# ZigUP.net
KiCad netlist of a schematic drawn in EAGLE
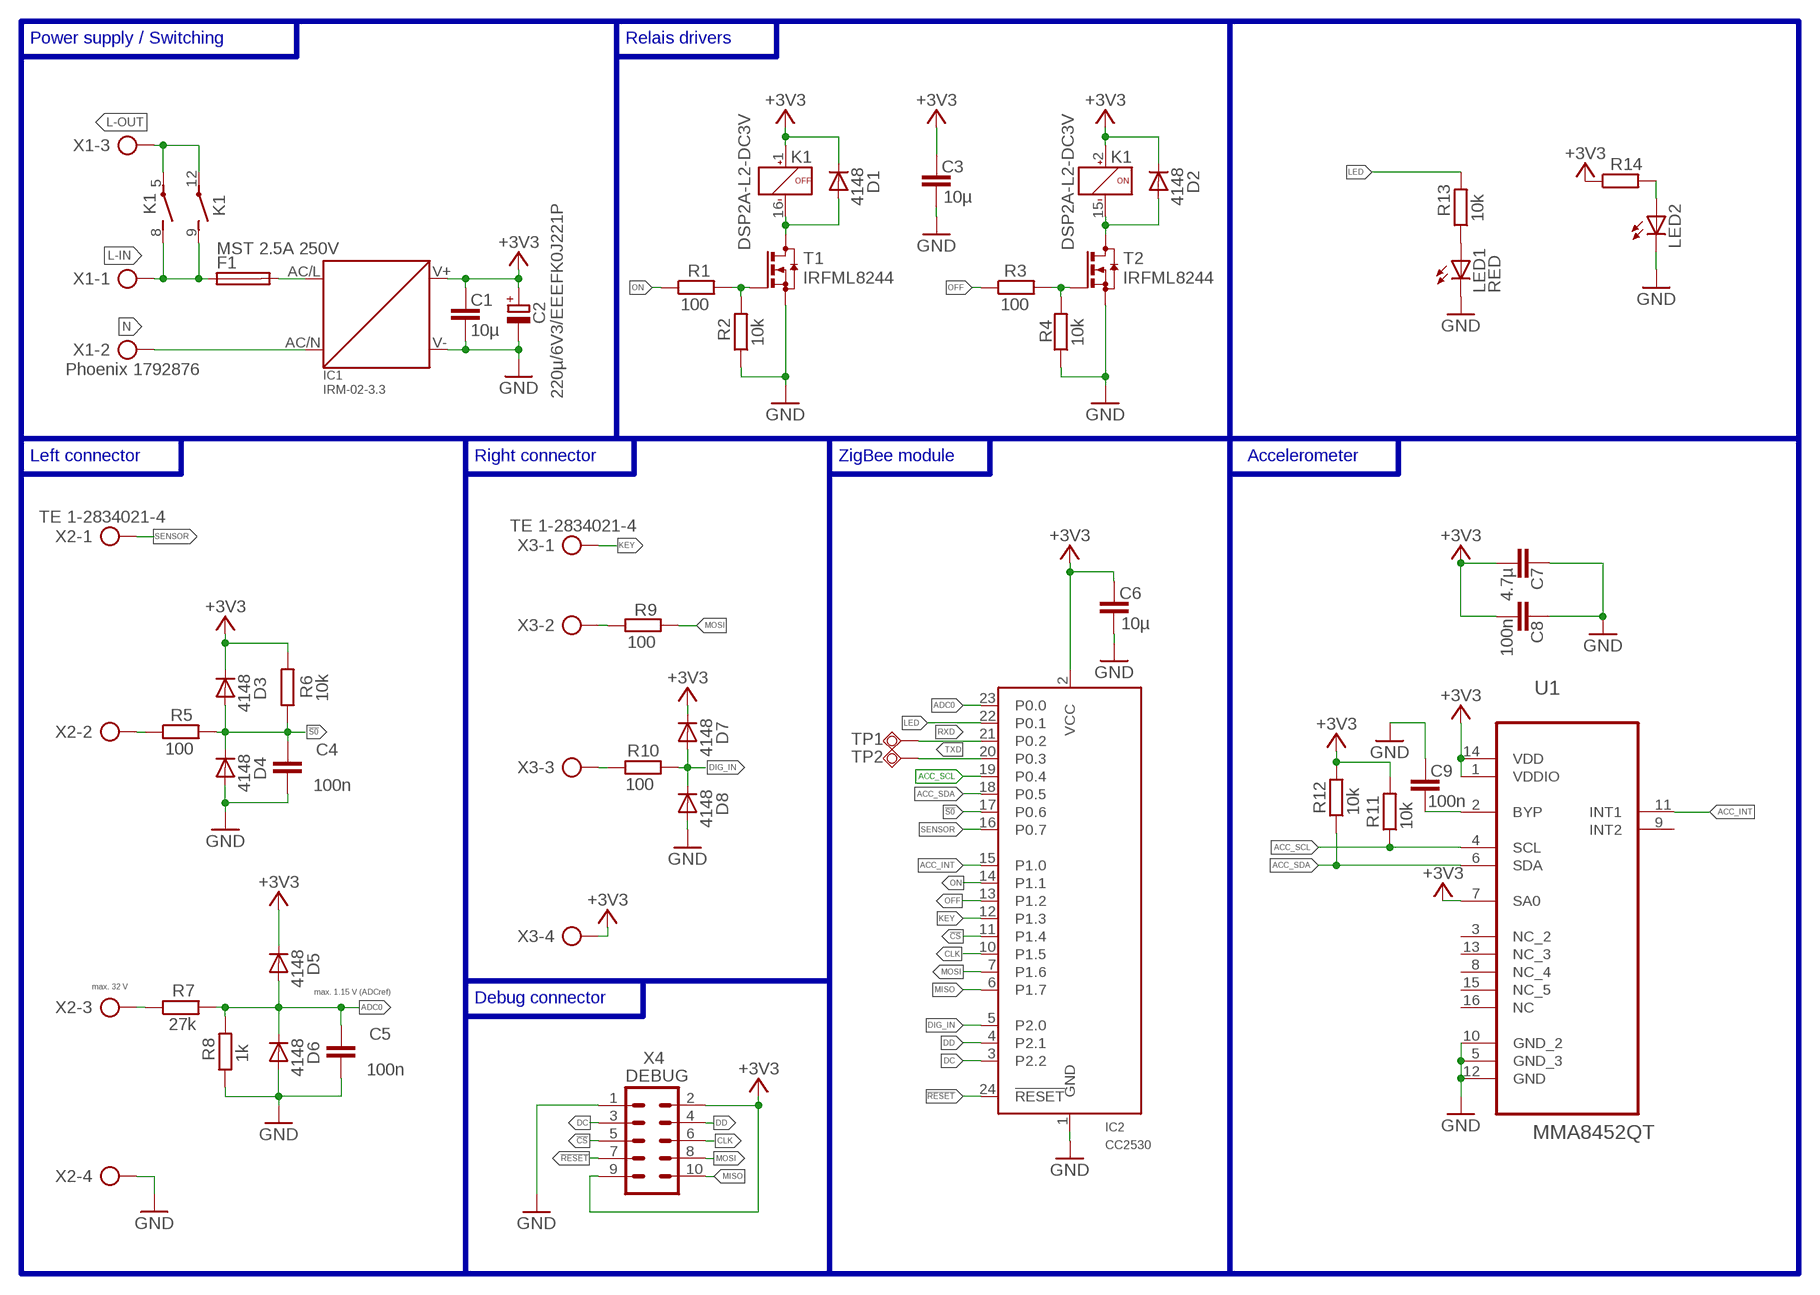
[diagram p0: schematic, sheet 1]

(export (version "E")
  (design (tool "Eeschema 10.0.6"))
  (components
    (comp (ref "C1")
      (value "10µ")
      (footprint "eagle-import:C0805")
      (libsource (lib "eagle-import") (part "C-EUC0805"))
    )
    (comp (ref "C2")
      (value "220µ/6V3/EEEFK0J221P")
      (footprint "eagle-import:E2,5-6")
      (libsource (lib "eagle-import") (part "CPOL-EUE2.5-6"))
    )
    (comp (ref "C3")
      (value "10µ")
      (footprint "eagle-import:C0805")
      (libsource (lib "eagle-import") (part "C-EUC0805"))
    )
    (comp (ref "C4")
      (value "100n")
      (footprint "eagle-import:C0805")
      (libsource (lib "eagle-import") (part "C-EUC0805"))
    )
    (comp (ref "C5")
      (value "100n")
      (footprint "eagle-import:C0805")
      (libsource (lib "eagle-import") (part "C-EUC0805"))
    )
    (comp (ref "C6")
      (value "10µ")
      (footprint "eagle-import:C0805")
      (libsource (lib "eagle-import") (part "C-EUC0805"))
    )
    (comp (ref "C7")
      (value "4.7µ")
      (footprint "eagle-import:C0805")
      (libsource (lib "eagle-import") (part "C-EUC0805"))
    )
    (comp (ref "C8")
      (value "100n")
      (footprint "eagle-import:C0805")
      (libsource (lib "eagle-import") (part "C-EUC0805"))
    )
    (comp (ref "C9")
      (value "100n")
      (footprint "eagle-import:C0805")
      (libsource (lib "eagle-import") (part "C-EUC0805"))
    )
    (comp (ref "D1")
      (value "4148")
      (footprint "eagle-import:1206")
      (libsource (lib "eagle-import") (part "TS4148"))
    )
    (comp (ref "D2")
      (value "4148")
      (footprint "eagle-import:1206")
      (libsource (lib "eagle-import") (part "TS4148"))
    )
    (comp (ref "D3")
      (value "4148")
      (footprint "eagle-import:1206")
      (libsource (lib "eagle-import") (part "TS4148"))
    )
    (comp (ref "D4")
      (value "4148")
      (footprint "eagle-import:1206")
      (libsource (lib "eagle-import") (part "TS4148"))
    )
    (comp (ref "D5")
      (value "4148")
      (footprint "eagle-import:1206")
      (libsource (lib "eagle-import") (part "TS4148"))
    )
    (comp (ref "D6")
      (value "4148")
      (footprint "eagle-import:1206")
      (libsource (lib "eagle-import") (part "TS4148"))
    )
    (comp (ref "D7")
      (value "4148")
      (footprint "eagle-import:1206")
      (libsource (lib "eagle-import") (part "TS4148"))
    )
    (comp (ref "D8")
      (value "4148")
      (footprint "eagle-import:1206")
      (libsource (lib "eagle-import") (part "TS4148"))
    )
    (comp (ref "F1")
      (value "MST 2.5A 250V")
      (footprint "eagle-import:MST")
      (libsource (lib "eagle-import") (part "MST"))
    )
    (comp (ref "IC1")
      (value "IRM-02-3.3")
      (footprint "eagle-import:IRM-01")
      (libsource (lib "eagle-import") (part "IRM-01"))
    )
    (comp (ref "IC2")
      (value "CC2530")
      (footprint "eagle-import:E18-MS1-PCB")
      (libsource (lib "eagle-import") (part "CC2530THT"))
    )
    (comp (ref "K1")
      (value "DSP2A-L2-DC3V")
      (footprint "eagle-import:DSP2A-L2")
      (libsource (lib "eagle-import") (part "DSP2A-L2"))
    )
    (comp (ref "LED1")
      (value "RED")
      (footprint "eagle-import:LED3MM")
      (libsource (lib "eagle-import") (part "LED3MM"))
    )
    (comp (ref "LED2")
      (value "LEDSML0805")
      (footprint "eagle-import:SML0805")
      (libsource (lib "eagle-import") (part "LEDSML0805"))
    )
    (comp (ref "R1")
      (value "100")
      (footprint "eagle-import:R0805")
      (libsource (lib "eagle-import") (part "R-EU_R0805"))
    )
    (comp (ref "R2")
      (value "10k")
      (footprint "eagle-import:R0805")
      (libsource (lib "eagle-import") (part "R-EU_R0805"))
    )
    (comp (ref "R3")
      (value "100")
      (footprint "eagle-import:R0805")
      (libsource (lib "eagle-import") (part "R-EU_R0805"))
    )
    (comp (ref "R4")
      (value "10k")
      (footprint "eagle-import:R0805")
      (libsource (lib "eagle-import") (part "R-EU_R0805"))
    )
    (comp (ref "R5")
      (value "100")
      (footprint "eagle-import:R0805")
      (libsource (lib "eagle-import") (part "R-EU_R0805"))
    )
    (comp (ref "R6")
      (value "10k")
      (footprint "eagle-import:R0805")
      (libsource (lib "eagle-import") (part "R-EU_R0805"))
    )
    (comp (ref "R7")
      (value "27k")
      (footprint "eagle-import:R0805")
      (libsource (lib "eagle-import") (part "R-EU_R0805"))
    )
    (comp (ref "R8")
      (value "1k")
      (footprint "eagle-import:R0805")
      (libsource (lib "eagle-import") (part "R-EU_R0805"))
    )
    (comp (ref "R9")
      (value "100")
      (footprint "eagle-import:R0805")
      (libsource (lib "eagle-import") (part "R-EU_R0805"))
    )
    (comp (ref "R10")
      (value "100")
      (footprint "eagle-import:R0805")
      (libsource (lib "eagle-import") (part "R-EU_R0805"))
    )
    (comp (ref "R11")
      (value "10k")
      (footprint "eagle-import:R0805")
      (libsource (lib "eagle-import") (part "R-EU_R0805"))
    )
    (comp (ref "R12")
      (value "10k")
      (footprint "eagle-import:R0805")
      (libsource (lib "eagle-import") (part "R-EU_R0805"))
    )
    (comp (ref "R13")
      (value "10k")
      (footprint "eagle-import:R0805")
      (libsource (lib "eagle-import") (part "R-EU_R0805"))
    )
    (comp (ref "R14")
      (value "R-EU_R0805")
      (footprint "eagle-import:R0805")
      (libsource (lib "eagle-import") (part "R-EU_R0805"))
    )
    (comp (ref "T1")
      (value "IRFML8244")
      (footprint "eagle-import:SOT23")
      (libsource (lib "eagle-import") (part "BSS123"))
    )
    (comp (ref "T2")
      (value "IRFML8244")
      (footprint "eagle-import:SOT23")
      (libsource (lib "eagle-import") (part "BSS123"))
    )
    (comp (ref "TP1")
      (value "RX")
      (footprint "eagle-import:TP15SQ")
      (libsource (lib "eagle-import") (part "TPSQTP15SQ"))
    )
    (comp (ref "TP2")
      (value "TX")
      (footprint "eagle-import:TP15SQ")
      (libsource (lib "eagle-import") (part "TPSQTP15SQ"))
    )
    (comp (ref "U1")
      (value "MMA8452QT")
      (footprint "eagle-import:QFN50P300X300X100-16N")
      (fields (field (name "MPN") "MMA8452QT "))
      (libsource (lib "eagle-import") (part "MMA8452QT"))
    )
    (comp (ref "X1")
      (value "Phoenix 1792876")
      (footprint "eagle-import:PTS-3")
      (libsource (lib "eagle-import") (part "PTS3"))
    )
    (comp (ref "X2")
      (value "TE 1-2834021-4")
      (footprint "eagle-import:MSC4")
      (libsource (lib "eagle-import") (part "MSC4"))
    )
    (comp (ref "X3")
      (value "TE 1-2834021-4")
      (footprint "eagle-import:MSC4")
      (libsource (lib "eagle-import") (part "MSC4"))
    )
    (comp (ref "X4")
      (value "DEBUG")
      (footprint "eagle-import:MA05-2")
      (libsource (lib "eagle-import") (part "MA05-2"))
    )
  )
  (nets
    (net (code "2") (name "+3V3") (class "Default")
      (node (ref "C1") (pin "1") (pinfunction "1_1") (pintype "passive"))
      (node (ref "C2") (pin "+") (pinfunction "+_+") (pintype "passive"))
      (node (ref "C3") (pin "1") (pinfunction "1_1") (pintype "passive"))
      (node (ref "C6") (pin "1") (pinfunction "1_1") (pintype "passive"))
      (node (ref "C7") (pin "2") (pinfunction "2_2") (pintype "passive"))
      (node (ref "C8") (pin "2") (pinfunction "2_2") (pintype "passive"))
      (node (ref "D1") (pin "K") (pinfunction "K_K") (pintype "passive"))
      (node (ref "D2") (pin "K") (pinfunction "K_K") (pintype "passive"))
      (node (ref "D3") (pin "K") (pinfunction "K_K") (pintype "passive"))
      (node (ref "D5") (pin "K") (pinfunction "K_K") (pintype "passive"))
      (node (ref "D7") (pin "K") (pinfunction "K_K") (pintype "passive"))
      (node (ref "IC1") (pin "V+") (pinfunction "V+_V+") (pintype "passive"))
      (node (ref "IC2") (pin "2") (pinfunction "VCC_2") (pintype "passive"))
      (node (ref "K1") (pin "1") (pinfunction "+_1") (pintype "passive"))
      (node (ref "K1") (pin "2") (pinfunction "+_2") (pintype "passive"))
      (node (ref "R11") (pin "2") (pinfunction "2_2") (pintype "passive"))
      (node (ref "R12") (pin "2") (pinfunction "2_2") (pintype "passive"))
      (node (ref "R14") (pin "1") (pinfunction "1_1") (pintype "passive"))
      (node (ref "R6") (pin "2") (pinfunction "2_2") (pintype "passive"))
      (node (ref "U1") (pin "1") (pinfunction "VDDIO_1") (pintype "power_in"))
      (node (ref "U1") (pin "14") (pinfunction "VDD_14") (pintype "power_in"))
      (node (ref "U1") (pin "7") (pinfunction "SA0_7") (pintype "input"))
      (node (ref "X3") (pin "4") (pinfunction "KL_4") (pintype "passive"))
      (node (ref "X4") (pin "2") (pinfunction "2_2") (pintype "passive"))
      (node (ref "X4") (pin "9") (pinfunction "9_9") (pintype "passive"))
    )
    (net (code "4") (name "/~{CS}") (class "Default")
      (node (ref "IC2") (pin "11") (pinfunction "P1.4_11") (pintype "passive"))
      (node (ref "X4") (pin "5") (pinfunction "5_5") (pintype "passive"))
    )
    (net (code "5") (name "/~{RESET}") (class "Default")
      (node (ref "IC2") (pin "24") (pinfunction "~{RESET}_24") (pintype "passive"))
      (node (ref "X4") (pin "7") (pinfunction "7_7") (pintype "passive"))
    )
    (net (code "6") (name "/~{S0}") (class "Default")
      (node (ref "C4") (pin "1") (pinfunction "1_1") (pintype "passive"))
      (node (ref "D3") (pin "A") (pinfunction "A_A") (pintype "passive"))
      (node (ref "D4") (pin "K") (pinfunction "K_K") (pintype "passive"))
      (node (ref "IC2") (pin "17") (pinfunction "P0.6_17") (pintype "passive"))
      (node (ref "R5") (pin "2") (pinfunction "2_2") (pintype "passive"))
      (node (ref "R6") (pin "1") (pinfunction "1_1") (pintype "passive"))
    )
    (net (code "7") (name "ACC_INT") (class "Default")
      (node (ref "IC2") (pin "15") (pinfunction "P1.0_15") (pintype "passive"))
      (node (ref "U1") (pin "11") (pinfunction "INT1_11") (pintype "output"))
    )
    (net (code "8") (name "ACC_SCL") (class "Default")
      (node (ref "IC2") (pin "19") (pinfunction "P0.4_19") (pintype "passive"))
      (node (ref "R11") (pin "1") (pinfunction "1_1") (pintype "passive"))
      (node (ref "U1") (pin "4") (pinfunction "SCL_4") (pintype "passive"))
    )
    (net (code "9") (name "ACC_SDA") (class "Default")
      (node (ref "IC2") (pin "18") (pinfunction "P0.5_18") (pintype "passive"))
      (node (ref "R12") (pin "1") (pinfunction "1_1") (pintype "passive"))
      (node (ref "U1") (pin "6") (pinfunction "SDA_6") (pintype "passive"))
    )
    (net (code "10") (name "ADC0") (class "Default")
      (node (ref "C5") (pin "1") (pinfunction "1_1") (pintype "passive"))
      (node (ref "D5") (pin "A") (pinfunction "A_A") (pintype "passive"))
      (node (ref "D6") (pin "K") (pinfunction "K_K") (pintype "passive"))
      (node (ref "IC2") (pin "23") (pinfunction "P0.0_23") (pintype "passive"))
      (node (ref "R7") (pin "2") (pinfunction "2_2") (pintype "passive"))
      (node (ref "R8") (pin "2") (pinfunction "2_2") (pintype "passive"))
    )
    (net (code "11") (name "CLK") (class "Default")
      (node (ref "IC2") (pin "10") (pinfunction "P1.5_10") (pintype "passive"))
      (node (ref "X4") (pin "6") (pinfunction "6_6") (pintype "passive"))
    )
    (net (code "12") (name "DC") (class "Default")
      (node (ref "IC2") (pin "3") (pinfunction "P2.2_3") (pintype "passive"))
      (node (ref "X4") (pin "3") (pinfunction "3_3") (pintype "passive"))
    )
    (net (code "13") (name "DD") (class "Default")
      (node (ref "IC2") (pin "4") (pinfunction "P2.1_4") (pintype "passive"))
      (node (ref "X4") (pin "4") (pinfunction "4_4") (pintype "passive"))
    )
    (net (code "14") (name "DIG_IN") (class "Default")
      (node (ref "D7") (pin "A") (pinfunction "A_A") (pintype "passive"))
      (node (ref "D8") (pin "K") (pinfunction "K_K") (pintype "passive"))
      (node (ref "IC2") (pin "5") (pinfunction "P2.0_5") (pintype "passive"))
      (node (ref "R10") (pin "2") (pinfunction "2_2") (pintype "passive"))
    )
    (net (code "15") (name "GND") (class "Default")
      (node (ref "C1") (pin "2") (pinfunction "2_2") (pintype "passive"))
      (node (ref "C2") (pin "-") (pinfunction "-_-") (pintype "passive"))
      (node (ref "C3") (pin "2") (pinfunction "2_2") (pintype "passive"))
      (node (ref "C4") (pin "2") (pinfunction "2_2") (pintype "passive"))
      (node (ref "C5") (pin "2") (pinfunction "2_2") (pintype "passive"))
      (node (ref "C6") (pin "2") (pinfunction "2_2") (pintype "passive"))
      (node (ref "C7") (pin "1") (pinfunction "1_1") (pintype "passive"))
      (node (ref "C8") (pin "1") (pinfunction "1_1") (pintype "passive"))
      (node (ref "C9") (pin "1") (pinfunction "1_1") (pintype "passive"))
      (node (ref "D4") (pin "A") (pinfunction "A_A") (pintype "passive"))
      (node (ref "D6") (pin "A") (pinfunction "A_A") (pintype "passive"))
      (node (ref "D8") (pin "A") (pinfunction "A_A") (pintype "passive"))
      (node (ref "IC1") (pin "V-") (pinfunction "V-_V-") (pintype "passive"))
      (node (ref "IC2") (pin "1") (pinfunction "GND_1") (pintype "passive"))
      (node (ref "LED1") (pin "K") (pinfunction "C_K") (pintype "passive"))
      (node (ref "LED2") (pin "C") (pinfunction "C_C") (pintype "passive"))
      (node (ref "R2") (pin "1") (pinfunction "1_1") (pintype "passive"))
      (node (ref "R4") (pin "1") (pinfunction "1_1") (pintype "passive"))
      (node (ref "R8") (pin "1") (pinfunction "1_1") (pintype "passive"))
      (node (ref "T1") (pin "2") (pinfunction "S_2") (pintype "passive"))
      (node (ref "T2") (pin "2") (pinfunction "S_2") (pintype "passive"))
      (node (ref "U1") (pin "10") (pinfunction "GND_2_10") (pintype "passive"))
      (node (ref "U1") (pin "12") (pinfunction "GND_12") (pintype "passive"))
      (node (ref "U1") (pin "5") (pinfunction "GND_3_5") (pintype "passive"))
      (node (ref "X2") (pin "4") (pinfunction "KL_4") (pintype "passive"))
      (node (ref "X4") (pin "1") (pinfunction "1_1") (pintype "passive"))
    )
    (net (code "16") (name "KEY") (class "Default")
      (node (ref "IC2") (pin "12") (pinfunction "P1.3_12") (pintype "passive"))
      (node (ref "X3") (pin "1") (pinfunction "KL_1") (pintype "passive"))
    )
    (net (code "17") (name "L-IN") (class "Default")
      (node (ref "F1") (pin "1") (pinfunction "1_1") (pintype "passive"))
      (node (ref "K1") (pin "8") (pinfunction "C_8") (pintype "passive"))
      (node (ref "K1") (pin "9") (pinfunction "C_9") (pintype "passive"))
      (node (ref "X1") (pin "1") (pinfunction "KL_1") (pintype "passive"))
    )
    (net (code "18") (name "L-OUT") (class "Default")
      (node (ref "K1") (pin "12") (pinfunction "S_12") (pintype "passive"))
      (node (ref "K1") (pin "5") (pinfunction "S_5") (pintype "passive"))
      (node (ref "X1") (pin "3") (pinfunction "KL_3") (pintype "passive"))
    )
    (net (code "19") (name "LED") (class "Default")
      (node (ref "IC2") (pin "22") (pinfunction "P0.1_22") (pintype "passive"))
      (node (ref "R13") (pin "2") (pinfunction "2_2") (pintype "passive"))
    )
    (net (code "20") (name "MISO") (class "Default")
      (node (ref "IC2") (pin "6") (pinfunction "P1.7_6") (pintype "passive"))
      (node (ref "X4") (pin "10") (pinfunction "10_10") (pintype "passive"))
    )
    (net (code "21") (name "MOSI") (class "Default")
      (node (ref "IC2") (pin "7") (pinfunction "P1.6_7") (pintype "passive"))
      (node (ref "R9") (pin "1") (pinfunction "1_1") (pintype "passive"))
      (node (ref "X4") (pin "8") (pinfunction "8_8") (pintype "passive"))
    )
    (net (code "22") (name "N") (class "Default")
      (node (ref "IC1") (pin "AC/N") (pinfunction "AC/N_AC/N") (pintype "passive"))
      (node (ref "X1") (pin "2") (pinfunction "KL_2") (pintype "passive"))
    )
    (net (code "23") (name "Net-(F1-Pad2)") (class "Default")
      (node (ref "F1") (pin "2") (pinfunction "2_2") (pintype "passive"))
      (node (ref "IC1") (pin "AC/L") (pinfunction "AC/L_AC/L") (pintype "passive"))
    )
    (net (code "24") (name "Net-(K1A--)") (class "Default")
      (node (ref "D1") (pin "A") (pinfunction "A_A") (pintype "passive"))
      (node (ref "K1") (pin "16") (pinfunction "-_16") (pintype "passive"))
      (node (ref "T1") (pin "3") (pinfunction "D_3") (pintype "passive"))
    )
    (net (code "25") (name "Net-(K1B--)") (class "Default")
      (node (ref "D2") (pin "A") (pinfunction "A_A") (pintype "passive"))
      (node (ref "K1") (pin "15") (pinfunction "-_15") (pintype "passive"))
      (node (ref "T2") (pin "3") (pinfunction "D_3") (pintype "passive"))
    )
    (net (code "26") (name "Net-(LED1-PadA)") (class "Default")
      (node (ref "LED1") (pin "A") (pinfunction "A_A") (pintype "passive"))
      (node (ref "R13") (pin "1") (pinfunction "1_1") (pintype "passive"))
    )
    (net (code "27") (name "Net-(LED2-PadA)") (class "Default")
      (node (ref "LED2") (pin "A") (pinfunction "A_A") (pintype "passive"))
      (node (ref "R14") (pin "2") (pinfunction "2_2") (pintype "passive"))
    )
    (net (code "28") (name "Net-(T1-G)") (class "Default")
      (node (ref "R1") (pin "2") (pinfunction "2_2") (pintype "passive"))
      (node (ref "R2") (pin "2") (pinfunction "2_2") (pintype "passive"))
      (node (ref "T1") (pin "1") (pinfunction "G_1") (pintype "passive"))
    )
    (net (code "29") (name "Net-(T2-G)") (class "Default")
      (node (ref "R3") (pin "2") (pinfunction "2_2") (pintype "passive"))
      (node (ref "R4") (pin "2") (pinfunction "2_2") (pintype "passive"))
      (node (ref "T2") (pin "1") (pinfunction "G_1") (pintype "passive"))
    )
    (net (code "30") (name "Net-(U1-BYP)") (class "Default")
      (node (ref "C9") (pin "2") (pinfunction "2_2") (pintype "passive"))
      (node (ref "U1") (pin "2") (pinfunction "BYP_2") (pintype "input"))
    )
    (net (code "31") (name "Net-(X2B-KL)") (class "Default")
      (node (ref "R5") (pin "1") (pinfunction "1_1") (pintype "passive"))
      (node (ref "X2") (pin "2") (pinfunction "KL_2") (pintype "passive"))
    )
    (net (code "32") (name "Net-(X2C-KL)") (class "Default")
      (node (ref "R7") (pin "1") (pinfunction "1_1") (pintype "passive"))
      (node (ref "X2") (pin "3") (pinfunction "KL_3") (pintype "passive"))
    )
    (net (code "33") (name "Net-(X3B-KL)") (class "Default")
      (node (ref "R9") (pin "2") (pinfunction "2_2") (pintype "passive"))
      (node (ref "X3") (pin "2") (pinfunction "KL_2") (pintype "passive"))
    )
    (net (code "34") (name "Net-(X3C-KL)") (class "Default")
      (node (ref "R10") (pin "1") (pinfunction "1_1") (pintype "passive"))
      (node (ref "X3") (pin "3") (pinfunction "KL_3") (pintype "passive"))
    )
    (net (code "35") (name "OFF") (class "Default")
      (node (ref "IC2") (pin "13") (pinfunction "P1.2_13") (pintype "passive"))
      (node (ref "R3") (pin "1") (pinfunction "1_1") (pintype "passive"))
    )
    (net (code "36") (name "ON") (class "Default")
      (node (ref "IC2") (pin "14") (pinfunction "P1.1_14") (pintype "passive"))
      (node (ref "R1") (pin "1") (pinfunction "1_1") (pintype "passive"))
    )
    (net (code "37") (name "RXD") (class "Default")
      (node (ref "IC2") (pin "21") (pinfunction "P0.2_21") (pintype "passive"))
      (node (ref "TP1") (pin "TP") (pinfunction "TP_TP") (pintype "input"))
    )
    (net (code "38") (name "SENSOR") (class "Default")
      (node (ref "IC2") (pin "16") (pinfunction "P0.7_16") (pintype "passive"))
      (node (ref "X2") (pin "1") (pinfunction "KL_1") (pintype "passive"))
    )
    (net (code "39") (name "TXD") (class "Default")
      (node (ref "IC2") (pin "20") (pinfunction "P0.3_20") (pintype "passive"))
      (node (ref "TP2") (pin "TP") (pinfunction "TP_TP") (pintype "input"))
    )
    (net (code "40") (name "unconnected-(U1-INT2-Pad9)") (class "Default")
      (node (ref "U1") (pin "9") (pinfunction "INT2_9") (pintype "output"))
    )
    (net (code "41") (name "unconnected-(U1-NC-Pad16)") (class "Default")
      (node (ref "U1") (pin "16") (pinfunction "NC_16") (pintype "no_connect"))
    )
    (net (code "42") (name "unconnected-(U1-NC_2-Pad3)") (class "Default")
      (node (ref "U1") (pin "3") (pinfunction "NC_2_3") (pintype "no_connect"))
    )
    (net (code "43") (name "unconnected-(U1-NC_3-Pad13)") (class "Default")
      (node (ref "U1") (pin "13") (pinfunction "NC_3_13") (pintype "no_connect"))
    )
    (net (code "44") (name "unconnected-(U1-NC_4-Pad8)") (class "Default")
      (node (ref "U1") (pin "8") (pinfunction "NC_4_8") (pintype "no_connect"))
    )
    (net (code "45") (name "unconnected-(U1-NC_5-Pad15)") (class "Default")
      (node (ref "U1") (pin "15") (pinfunction "NC_5_15") (pintype "no_connect"))
    )
  )
)
